# tuerklingel.net
KiCad netlist of a schematic drawn in EAGLE
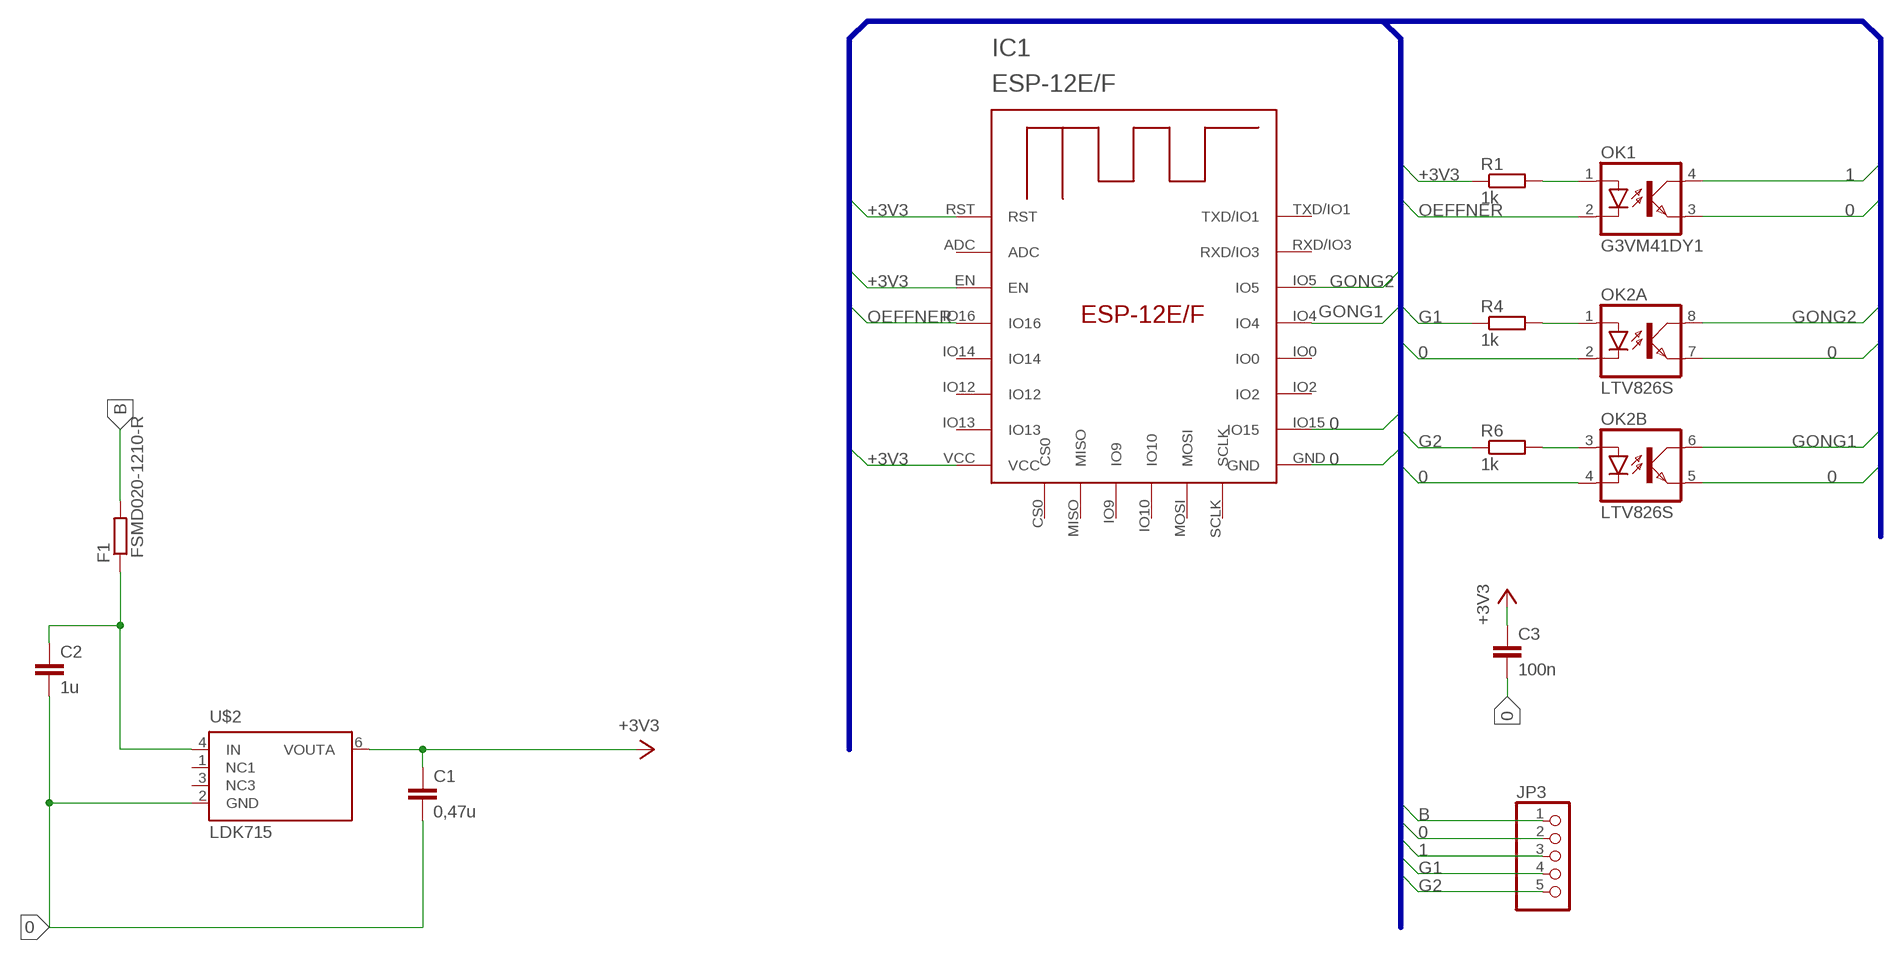
[diagram p0: schematic, sheet 1]

(export (version "E")
  (design (tool "Eeschema 10.0.6"))
  (components
    (comp (ref "C1")
      (value "0,47u")
      (footprint "eagle-import:C0805")
      (libsource (lib "eagle-import") (part "C-EUC0805"))
    )
    (comp (ref "C2")
      (value "1u")
      (footprint "eagle-import:C0805")
      (libsource (lib "eagle-import") (part "C-EUC0805"))
    )
    (comp (ref "C3")
      (value "100n")
      (footprint "eagle-import:C0805")
      (libsource (lib "eagle-import") (part "C-EUC0805"))
    )
    (comp (ref "F1")
      (value "FSMD020-1210-R")
      (footprint "eagle-import:R1210")
      (libsource (lib "eagle-import") (part "resistor_R-EU_R1210"))
    )
    (comp (ref "IC1")
      (value "ESP-12E/F")
      (footprint "eagle-import:ESP-12E")
      (libsource (lib "eagle-import") (part "ESP-12E/F"))
    )
    (comp (ref "JP3")
      (value "PINHD-1X5")
      (footprint "eagle-import:1X05")
      (libsource (lib "eagle-import") (part "PINHD-1X5"))
    )
    (comp (ref "OK1")
      (value "G3VM41DY1")
      (footprint "eagle-import:DIL4-SMD")
      (libsource (lib "eagle-import") (part "LTV816S"))
    )
    (comp (ref "OK2")
      (value "LTV826S")
      (footprint "eagle-import:DIL8-SMD")
      (libsource (lib "eagle-import") (part "LTV826S"))
    )
    (comp (ref "R1")
      (value "1k")
      (footprint "eagle-import:R0805")
      (libsource (lib "eagle-import") (part "R-EU_R0805"))
    )
    (comp (ref "R4")
      (value "1k")
      (footprint "eagle-import:R0805")
      (libsource (lib "eagle-import") (part "R-EU_R0805"))
    )
    (comp (ref "R6")
      (value "1k")
      (footprint "eagle-import:R0805")
      (libsource (lib "eagle-import") (part "R-EU_R0805"))
    )
    (comp (ref "U$2")
      (value "LDK715")
      (footprint "eagle-import:SOT23-6")
      (libsource (lib "eagle-import") (part "LDK715"))
    )
  )
  (nets
    (net (code "1") (name "+3V3") (class "Default")
      (node (ref "C1") (pin "1") (pinfunction "1_1") (pintype "passive"))
      (node (ref "C3") (pin "1") (pinfunction "1_1") (pintype "passive"))
      (node (ref "IC1") (pin "EN") (pinfunction "EN_EN") (pintype "bidirectional"))
      (node (ref "IC1") (pin "RST") (pinfunction "RST_RST") (pintype "input"))
      (node (ref "IC1") (pin "VCC") (pinfunction "VCC_VCC") (pintype "power_in"))
      (node (ref "R1") (pin "1") (pinfunction "1_1") (pintype "passive"))
      (node (ref "U$2") (pin "6") (pinfunction "VOUTA_6") (pintype "bidirectional"))
    )
    (net (code "2") (name "/1") (class "Default")
      (node (ref "JP3") (pin "3") (pinfunction "3_3") (pintype "passive"))
      (node (ref "OK1") (pin "4") (pinfunction "COL_4") (pintype "passive"))
    )
    (net (code "3") (name "/G1") (class "Default")
      (node (ref "JP3") (pin "4") (pinfunction "4_4") (pintype "passive"))
      (node (ref "R4") (pin "1") (pinfunction "1_1") (pintype "passive"))
    )
    (net (code "4") (name "/G2") (class "Default")
      (node (ref "JP3") (pin "5") (pinfunction "5_5") (pintype "passive"))
      (node (ref "R6") (pin "1") (pinfunction "1_1") (pintype "passive"))
    )
    (net (code "5") (name "/GONG1") (class "Default")
      (node (ref "IC1") (pin "IO4") (pinfunction "IO4_IO4") (pintype "bidirectional"))
      (node (ref "OK2") (pin "6") (pinfunction "COL_6") (pintype "passive"))
    )
    (net (code "6") (name "/GONG2") (class "Default")
      (node (ref "IC1") (pin "IO5") (pinfunction "IO5_IO5") (pintype "bidirectional"))
      (node (ref "OK2") (pin "8") (pinfunction "COL_8") (pintype "passive"))
    )
    (net (code "7") (name "/OEFFNER") (class "Default")
      (node (ref "IC1") (pin "IO16") (pinfunction "IO16_IO16") (pintype "bidirectional"))
      (node (ref "OK1") (pin "2") (pinfunction "C_2") (pintype "passive"))
    )
    (net (code "8") (name "0") (class "Default")
      (node (ref "C1") (pin "2") (pinfunction "2_2") (pintype "passive"))
      (node (ref "C2") (pin "2") (pinfunction "2_2") (pintype "passive"))
      (node (ref "C3") (pin "2") (pinfunction "2_2") (pintype "passive"))
      (node (ref "IC1") (pin "GND") (pinfunction "GND_GND") (pintype "power_in"))
      (node (ref "IC1") (pin "IO15") (pinfunction "IO15_IO15") (pintype "bidirectional"))
      (node (ref "JP3") (pin "2") (pinfunction "2_2") (pintype "passive"))
      (node (ref "OK1") (pin "3") (pinfunction "EMIT_3") (pintype "passive"))
      (node (ref "OK2") (pin "2") (pinfunction "C_2") (pintype "passive"))
      (node (ref "OK2") (pin "4") (pinfunction "C_4") (pintype "passive"))
      (node (ref "OK2") (pin "5") (pinfunction "EMIT_5") (pintype "passive"))
      (node (ref "OK2") (pin "7") (pinfunction "EMIT_7") (pintype "passive"))
      (node (ref "U$2") (pin "2") (pinfunction "GND_2") (pintype "bidirectional"))
    )
    (net (code "9") (name "B") (class "Default")
      (node (ref "F1") (pin "2") (pinfunction "2_2") (pintype "passive"))
      (node (ref "JP3") (pin "1") (pinfunction "1_1") (pintype "passive"))
    )
    (net (code "10") (name "Net-(OK1-A)") (class "Default")
      (node (ref "OK1") (pin "1") (pinfunction "A_1") (pintype "passive"))
      (node (ref "R1") (pin "2") (pinfunction "2_2") (pintype "passive"))
    )
    (net (code "11") (name "Net-(OK2A-A)") (class "Default")
      (node (ref "OK2") (pin "1") (pinfunction "A_1") (pintype "passive"))
      (node (ref "R4") (pin "2") (pinfunction "2_2") (pintype "passive"))
    )
    (net (code "12") (name "Net-(OK2B-A)") (class "Default")
      (node (ref "OK2") (pin "3") (pinfunction "A_3") (pintype "passive"))
      (node (ref "R6") (pin "2") (pinfunction "2_2") (pintype "passive"))
    )
    (net (code "13") (name "Net-(U$2-IN)") (class "Default")
      (node (ref "C2") (pin "1") (pinfunction "1_1") (pintype "passive"))
      (node (ref "F1") (pin "1") (pinfunction "1_1") (pintype "passive"))
      (node (ref "U$2") (pin "4") (pinfunction "IN_4") (pintype "power_in"))
    )
    (net (code "14") (name "unconnected-(IC1-PadADC)") (class "Default")
      (node (ref "IC1") (pin "ADC") (pinfunction "ADC_ADC") (pintype "bidirectional"))
    )
    (net (code "15") (name "unconnected-(IC1-PadCS0)") (class "Default")
      (node (ref "IC1") (pin "CS0") (pinfunction "CS0_CS0") (pintype "bidirectional"))
    )
    (net (code "16") (name "unconnected-(IC1-PadIO0)") (class "Default")
      (node (ref "IC1") (pin "IO0") (pinfunction "IO0_IO0") (pintype "bidirectional"))
    )
    (net (code "17") (name "unconnected-(IC1-PadIO2)") (class "Default")
      (node (ref "IC1") (pin "IO2") (pinfunction "IO2_IO2") (pintype "bidirectional"))
    )
    (net (code "18") (name "unconnected-(IC1-PadIO9)") (class "Default")
      (node (ref "IC1") (pin "IO9") (pinfunction "IO9_IO9") (pintype "bidirectional"))
    )
    (net (code "19") (name "unconnected-(IC1-PadIO10)") (class "Default")
      (node (ref "IC1") (pin "IO10") (pinfunction "IO10_IO10") (pintype "bidirectional"))
    )
    (net (code "20") (name "unconnected-(IC1-PadIO12)") (class "Default")
      (node (ref "IC1") (pin "IO12") (pinfunction "IO12_IO12") (pintype "bidirectional"))
    )
    (net (code "21") (name "unconnected-(IC1-PadIO13)") (class "Default")
      (node (ref "IC1") (pin "IO13") (pinfunction "IO13_IO13") (pintype "bidirectional"))
    )
    (net (code "22") (name "unconnected-(IC1-PadIO14)") (class "Default")
      (node (ref "IC1") (pin "IO14") (pinfunction "IO14_IO14") (pintype "bidirectional"))
    )
    (net (code "23") (name "unconnected-(IC1-PadMISO)") (class "Default")
      (node (ref "IC1") (pin "MISO") (pinfunction "MISO_MISO") (pintype "bidirectional"))
    )
    (net (code "24") (name "unconnected-(IC1-PadMOSI)") (class "Default")
      (node (ref "IC1") (pin "MOSI") (pinfunction "MOSI_MOSI") (pintype "bidirectional"))
    )
    (net (code "25") (name "unconnected-(IC1-PadRXD{slash}IO3)") (class "Default")
      (node (ref "IC1") (pin "RXD/IO3") (pinfunction "RXD/IO3_RXD/IO3") (pintype "bidirectional"))
    )
    (net (code "26") (name "unconnected-(IC1-PadSCLK)") (class "Default")
      (node (ref "IC1") (pin "SCLK") (pinfunction "SCLK_SCLK") (pintype "bidirectional"))
    )
    (net (code "27") (name "unconnected-(IC1-PadTXD{slash}IO1)") (class "Default")
      (node (ref "IC1") (pin "TXD/IO1") (pinfunction "TXD/IO1_TXD/IO1") (pintype "bidirectional"))
    )
    (net (code "28") (name "unconnected-(U$2-NC1-Pad1)") (class "Default")
      (node (ref "U$2") (pin "1") (pinfunction "NC1_1") (pintype "bidirectional"))
    )
    (net (code "29") (name "unconnected-(U$2-NC3-Pad3)") (class "Default")
      (node (ref "U$2") (pin "3") (pinfunction "NC3_3") (pintype "bidirectional"))
    )
  )
)
